# SparkFun_HMC5883L_Breakout.net
KiCad netlist of a schematic drawn in EAGLE
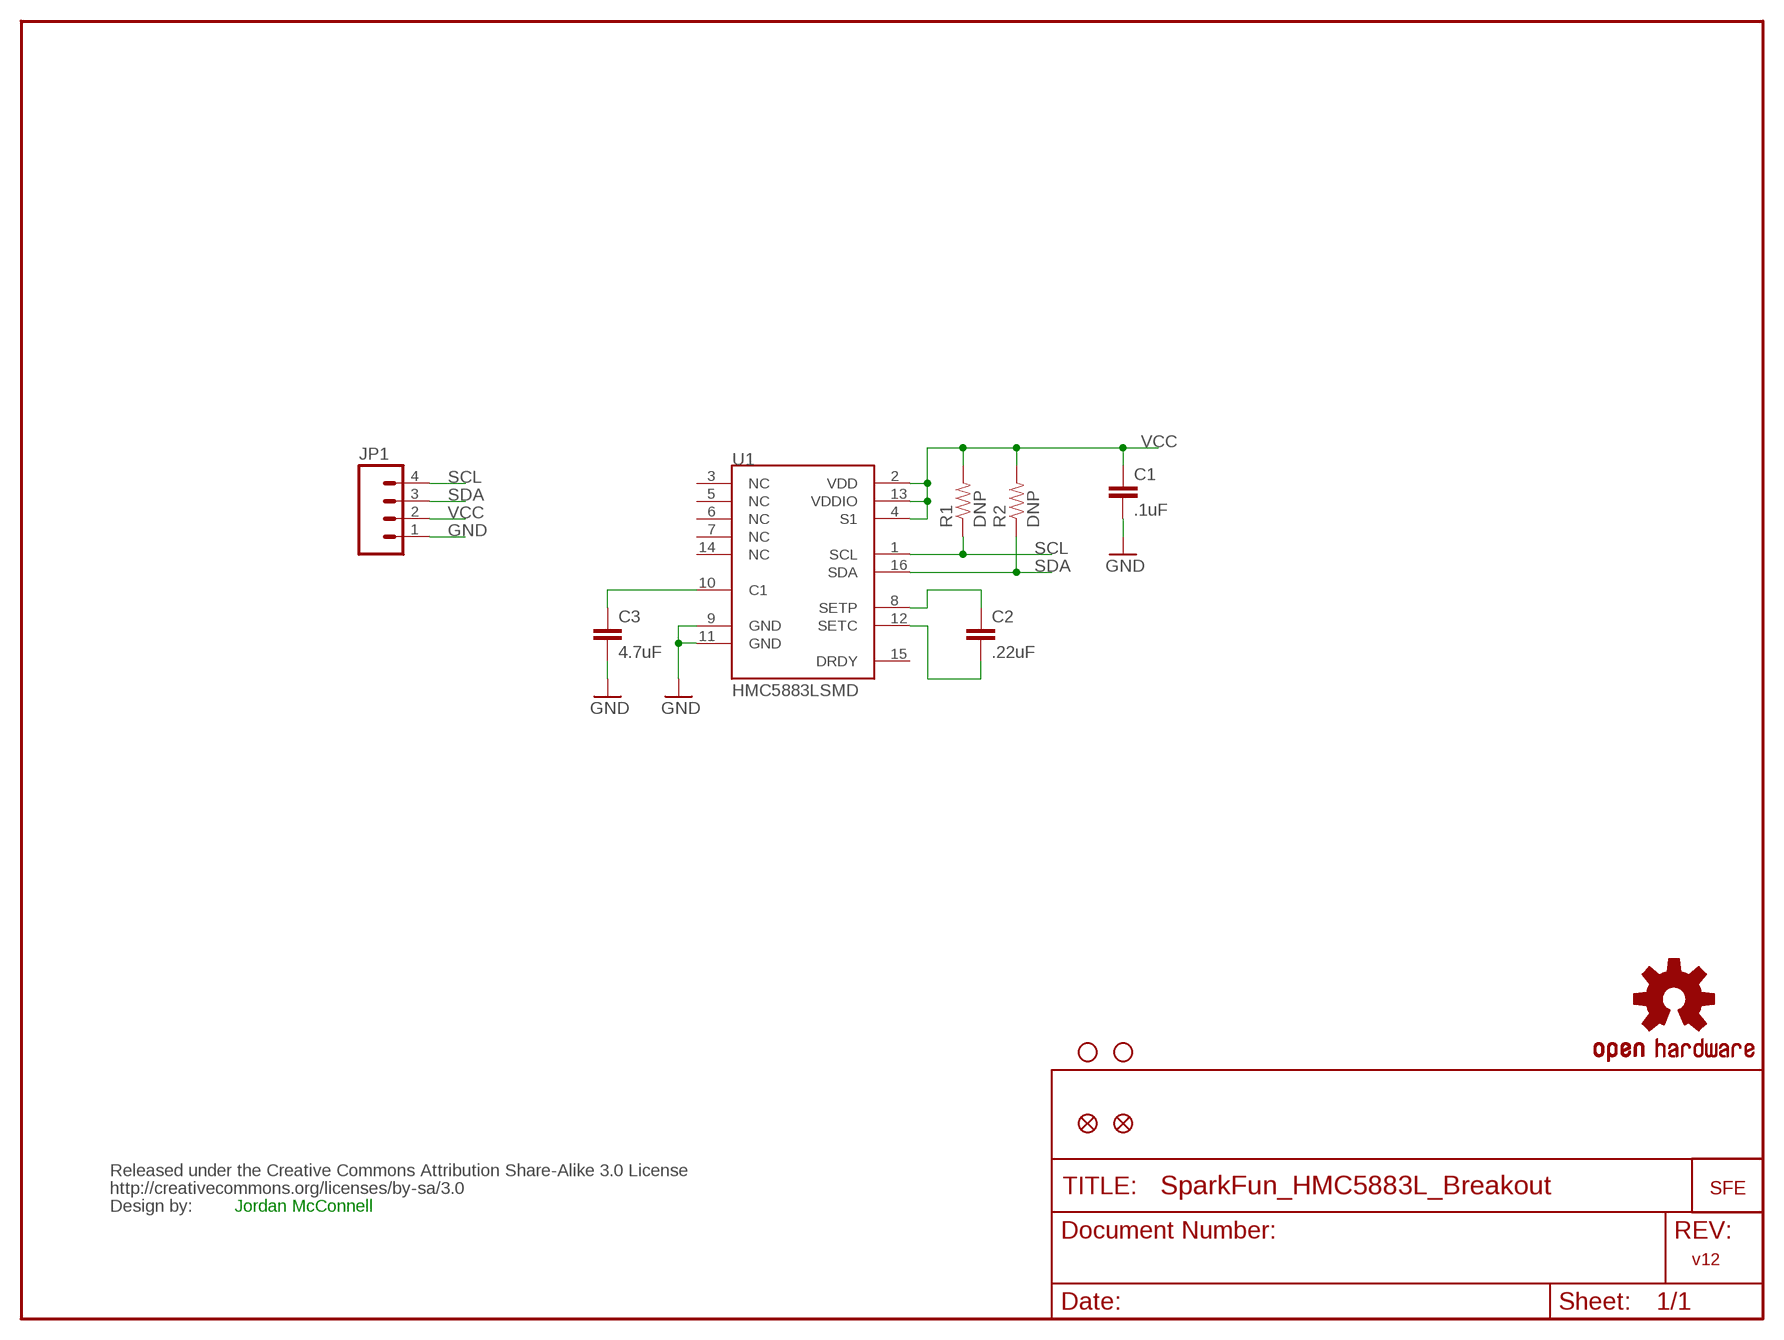
[diagram p0: schematic, sheet 1]

(export (version "E")
  (design (tool "Eeschema 10.0.6"))
  (components
    (comp (ref "C1")
      (value ".1uF")
      (footprint "eagle-import:0402-CAP")
      (libsource (lib "eagle-import") (part "CAP0402-CAP"))
    )
    (comp (ref "C2")
      (value ".22uF")
      (footprint "eagle-import:0402-CAP")
      (libsource (lib "eagle-import") (part "CAP0402-CAP"))
    )
    (comp (ref "C3")
      (value "4.7uF")
      (footprint "eagle-import:0402-CAP")
      (libsource (lib "eagle-import") (part "CAP0402-CAP"))
    )
    (comp (ref "JP1")
      (value "M04PTH")
      (footprint "eagle-import:1X04")
      (libsource (lib "eagle-import") (part "M04PTH"))
    )
    (comp (ref "JP2")
      (value "STAND-OFF")
      (footprint "eagle-import:STAND-OFF")
      (libsource (lib "eagle-import") (part "STAND-OFF"))
    )
    (comp (ref "JP3")
      (value "STAND-OFF")
      (footprint "eagle-import:STAND-OFF")
      (libsource (lib "eagle-import") (part "STAND-OFF"))
    )
    (comp (ref "JP4")
      (value "LOGO-SFESK")
      (footprint "eagle-import:SFE-LOGO-FLAME")
      (libsource (lib "eagle-import") (part "LOGO-SFESK"))
    )
    (comp (ref "JP5")
      (value "FIDUCIAL1X2.5")
      (footprint "eagle-import:FIDUCIAL-1X2.5")
      (libsource (lib "eagle-import") (part "FIDUCIAL1X2.5"))
    )
    (comp (ref "JP6")
      (value "FIDUCIAL1X2.5")
      (footprint "eagle-import:FIDUCIAL-1X2.5")
      (libsource (lib "eagle-import") (part "FIDUCIAL1X2.5"))
    )
    (comp (ref "R1")
      (value "DNP")
      (footprint "eagle-import:0402-RES")
      (libsource (lib "eagle-import") (part "RESISTOR0402-RES"))
    )
    (comp (ref "R2")
      (value "DNP")
      (footprint "eagle-import:0402-RES")
      (libsource (lib "eagle-import") (part "RESISTOR0402-RES"))
    )
    (comp (ref "U$1")
      (value "CREATIVE_COMMONS")
      (footprint "eagle-import:CREATIVE_COMMONS")
      (libsource (lib "eagle-import") (part "CREATIVE_COMMONS"))
    )
    (comp (ref "U$2")
      (value "OSHW-LOGOM")
      (footprint "eagle-import:OSHW-LOGO-M")
      (libsource (lib "eagle-import") (part "OSHW-LOGOM"))
    )
    (comp (ref "U1")
      (value "HMC5883LSMD")
      (footprint "eagle-import:16LPCC")
      (libsource (lib "eagle-import") (part "HMC5883LSMD"))
    )
  )
  (nets
    (net (code "1") (name "/SCL") (class "Default")
      (node (ref "JP1") (pin "4") (pinfunction "4_4") (pintype "passive"))
      (node (ref "R1") (pin "1") (pinfunction "1_1") (pintype "passive"))
      (node (ref "U1") (pin "1") (pinfunction "SCL_1") (pintype "bidirectional"))
    )
    (net (code "2") (name "/SDA") (class "Default")
      (node (ref "JP1") (pin "3") (pinfunction "3_3") (pintype "passive"))
      (node (ref "R2") (pin "1") (pinfunction "1_1") (pintype "passive"))
      (node (ref "U1") (pin "16") (pinfunction "SDA_16") (pintype "bidirectional"))
    )
    (net (code "3") (name "/VCC") (class "Default")
      (node (ref "C1") (pin "1") (pinfunction "1_1") (pintype "passive"))
      (node (ref "JP1") (pin "2") (pinfunction "2_2") (pintype "passive"))
      (node (ref "R1") (pin "2") (pinfunction "2_2") (pintype "passive"))
      (node (ref "R2") (pin "2") (pinfunction "2_2") (pintype "passive"))
      (node (ref "U1") (pin "13") (pinfunction "VDDIO_13") (pintype "bidirectional"))
      (node (ref "U1") (pin "2") (pinfunction "VDD_2") (pintype "bidirectional"))
      (node (ref "U1") (pin "4") (pinfunction "S1_4") (pintype "bidirectional"))
    )
    (net (code "4") (name "GND") (class "Default")
      (node (ref "C1") (pin "2") (pinfunction "2_2") (pintype "passive"))
      (node (ref "C3") (pin "2") (pinfunction "2_2") (pintype "passive"))
      (node (ref "JP1") (pin "1") (pinfunction "1_1") (pintype "passive"))
      (node (ref "U1") (pin "11") (pinfunction "GND_11") (pintype "bidirectional"))
      (node (ref "U1") (pin "9") (pinfunction "GND_9") (pintype "bidirectional"))
    )
    (net (code "5") (name "Net-(U1-C1)") (class "Default")
      (node (ref "C3") (pin "1") (pinfunction "1_1") (pintype "passive"))
      (node (ref "U1") (pin "10") (pinfunction "C1_10") (pintype "bidirectional"))
    )
    (net (code "6") (name "Net-(U1-SETC)") (class "Default")
      (node (ref "C2") (pin "2") (pinfunction "2_2") (pintype "passive"))
      (node (ref "U1") (pin "12") (pinfunction "SETC_12") (pintype "bidirectional"))
    )
    (net (code "7") (name "Net-(U1-SETP)") (class "Default")
      (node (ref "C2") (pin "1") (pinfunction "1_1") (pintype "passive"))
      (node (ref "U1") (pin "8") (pinfunction "SETP_8") (pintype "bidirectional"))
    )
    (net (code "8") (name "unconnected-(U1-DRDY-Pad15)") (class "Default")
      (node (ref "U1") (pin "15") (pinfunction "DRDY_15") (pintype "bidirectional"))
    )
    (net (code "9") (name "unconnected-(U1-NC-Pad3)") (class "Default")
      (node (ref "U1") (pin "3") (pinfunction "NC_3") (pintype "bidirectional"))
    )
    (net (code "10") (name "unconnected-(U1-NC-Pad5)") (class "Default")
      (node (ref "U1") (pin "5") (pinfunction "NC_5") (pintype "bidirectional"))
    )
    (net (code "11") (name "unconnected-(U1-NC-Pad6)") (class "Default")
      (node (ref "U1") (pin "6") (pinfunction "NC_6") (pintype "bidirectional"))
    )
    (net (code "12") (name "unconnected-(U1-NC-Pad7)") (class "Default")
      (node (ref "U1") (pin "7") (pinfunction "NC_7") (pintype "bidirectional"))
    )
    (net (code "13") (name "unconnected-(U1-NC-Pad14)") (class "Default")
      (node (ref "U1") (pin "14") (pinfunction "NC_14") (pintype "bidirectional"))
    )
  )
)
